# MAIN_STM32L476RGT6.net
KiCad netlist of a schematic drawn in Altium Designer
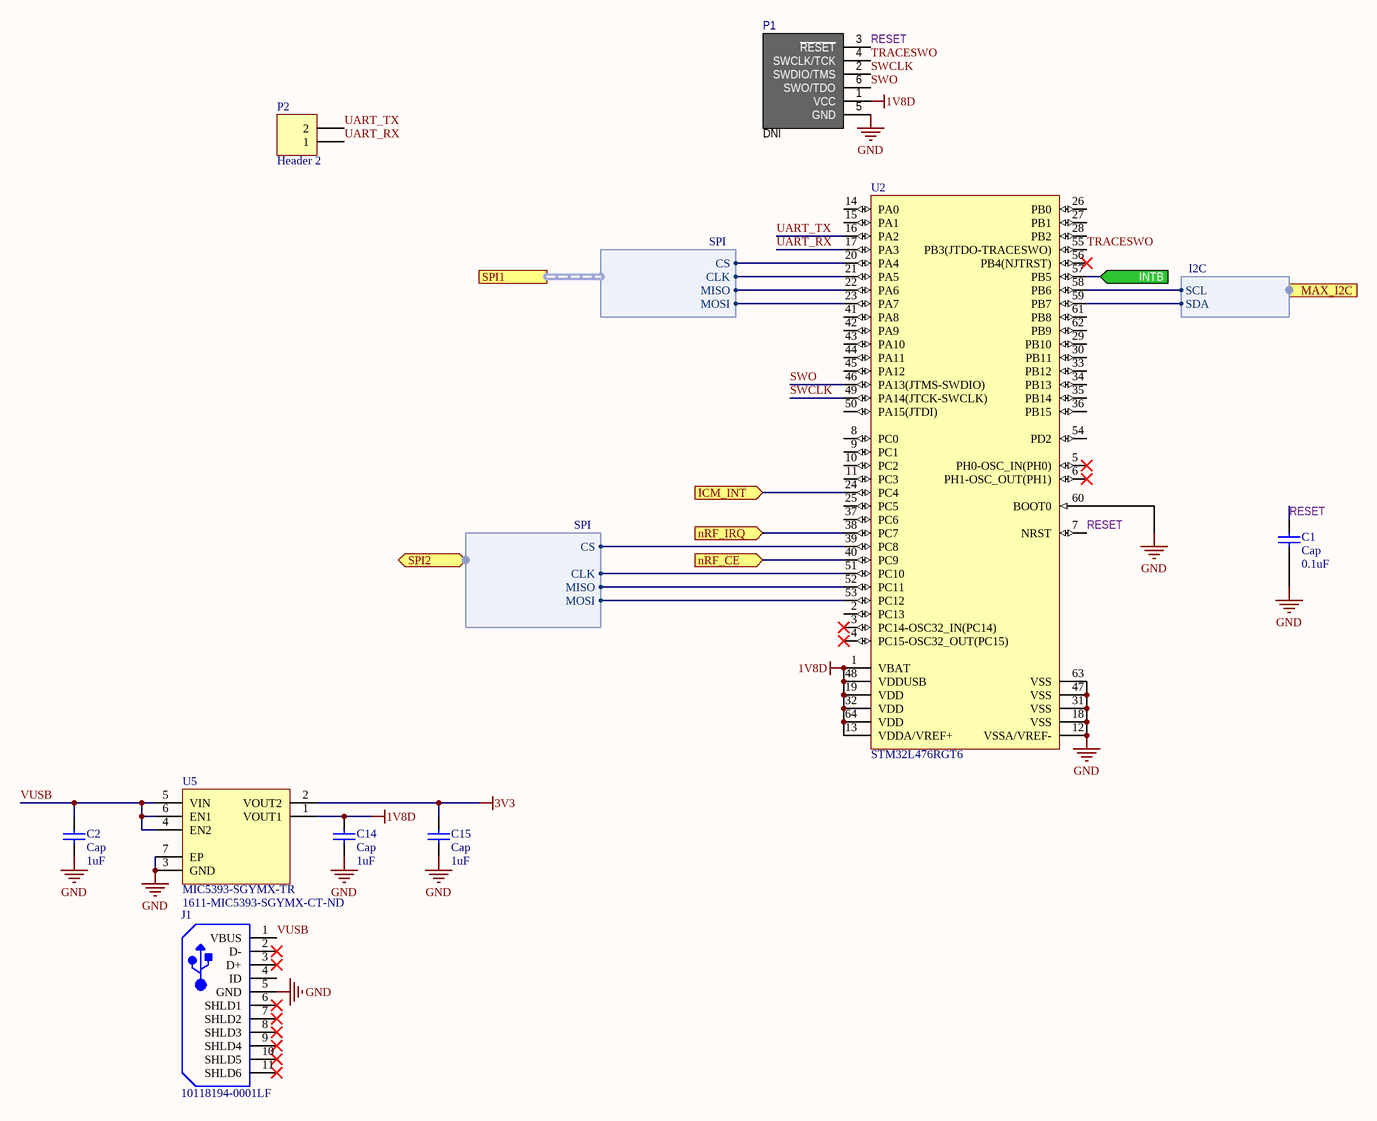
[diagram p0: MAIN_STM32L476RGT6.SchDoc]

(export (version "E")
  (design (tool "Eeschema 10.0.6"))
  (components
    (comp (ref "C1")
      (value "Cap")
      (footprint "CAPC1005N")
      (description "Capacitor")
      (fields (field (name "ALTIUM_VALUE") "0.1uF") (field (name "PUBLISHER") "Altium Limited"))
      (libsource (lib "Miscellaneous Devices") (part "Cap"))
    )
    (comp (ref "C2")
      (value "Cap")
      (footprint "CAPC1005N")
      (description "Capacitor")
      (fields (field (name "ALTIUM_VALUE") "1uF") (field (name "PUBLISHER") "Altium Limited"))
      (libsource (lib "Miscellaneous Devices") (part "Cap"))
    )
    (comp (ref "C14")
      (value "Cap")
      (footprint "CAPC1005N")
      (description "Capacitor")
      (fields (field (name "ALTIUM_VALUE") "1uF") (field (name "PUBLISHER") "Altium Limited"))
      (libsource (lib "Miscellaneous Devices") (part "Cap"))
    )
    (comp (ref "C15")
      (value "Cap")
      (footprint "CAPC1005N")
      (description "Capacitor")
      (fields (field (name "ALTIUM_VALUE") "1uF") (field (name "PUBLISHER") "Altium Limited"))
      (libsource (lib "Miscellaneous Devices") (part "Cap"))
    )
    (comp (ref "J1")
      (value "10118194-0001LF")
      (footprint "FCI-10118194-0001LF-5_V")
      (description "Micro USB B Type Receptacle, 1.8 A, -55 to 85 degC, 5-Pin SMD, RoHS, Tape and Reel")
      (fields (field (name "MANUFACTURER") "Amphenol FCI"))
      (libsource (lib "Altium Content Vault") (part "USB-5-6SHLD"))
    )
    (comp (ref "P1") (value "DNI") (footprint "TC2030") (libsource (lib "TagConnect") (part "TC2030-CTX")))
    (comp (ref "P2")
      (value "Header 2")
      (footprint "HDR1X2-PINS")
      (description "Header, 2-Pin")
      (fields (field (name "PUBLISHER") "Altium Limited"))
      (libsource (lib "Miscellaneous Connectors") (part "Header 2"))
    )
    (comp (ref "U2")
      (value "STM32L476RGT6")
      (footprint "STM-LQFP64_N")
      (fields (field (name "MANUFACTURER") "STMicroelectronics"))
      (libsource (lib "Altium Content Vault") (part "MC-ARM-STM32L4X6-LQFP64"))
    )
    (comp (ref "U5")
      (value "MIC5393-SGYMX-TR")
      (footprint "MIC5392")
      (description "IC REG LINEAR 1.8V/3.3V 6XTDFN")
      (fields (field (name "SUPPLIER PART NUMBER 1") "1611-MIC5393-SGYMX-CT-ND"))
      (libsource (lib "Schlib1") (part "MIC5393-SGYMX-TR"))
    )
  )
  (nets
    (net (code "3") (name "/ICM_INT") (class "Default")
      (node (ref "U2") (pin "24") (pinfunction "PC4_24") (pintype "bidirectional"))
    )
    (net (code "4") (name "/INTB") (class "Default")
      (node (ref "U2") (pin "57") (pinfunction "PB5_57") (pintype "bidirectional"))
    )
    (net (code "5") (name "/RESET") (class "Default")
      (node (ref "C1") (pin "2") (pinfunction "2_2") (pintype "passive"))
      (node (ref "P1") (pin "3") (pinfunction "~{RESET}_3") (pintype "passive"))
      (node (ref "U2") (pin "7") (pinfunction "NRST_7") (pintype "bidirectional"))
    )
    (net (code "6") (name "/SCL") (class "Default")
      (node (ref "U2") (pin "58") (pinfunction "PB6_58") (pintype "bidirectional"))
    )
    (net (code "7") (name "/SDA") (class "Default")
      (node (ref "U2") (pin "59") (pinfunction "PB7_59") (pintype "bidirectional"))
    )
    (net (code "8") (name "/SWCLK") (class "Default")
      (node (ref "P1") (pin "2") (pinfunction "SWDIO/TMS_2") (pintype "passive"))
      (node (ref "U2") (pin "49") (pinfunction "PA14(JTCK-SWCLK)_49") (pintype "bidirectional"))
    )
    (net (code "9") (name "/SWO") (class "Default")
      (node (ref "P1") (pin "6") (pinfunction "SWO/TDO_6") (pintype "passive"))
      (node (ref "U2") (pin "46") (pinfunction "PA13(JTMS-SWDIO)_46") (pintype "bidirectional"))
    )
    (net (code "10") (name "/TRACESWO") (class "Default")
      (node (ref "P1") (pin "4") (pinfunction "SWCLK/TCK_4") (pintype "passive"))
      (node (ref "U2") (pin "55") (pinfunction "PB3(JTDO-TRACESWO)_55") (pintype "bidirectional"))
    )
    (net (code "11") (name "/UART_RX") (class "Default")
      (node (ref "P2") (pin "1") (pinfunction "1_1") (pintype "passive"))
      (node (ref "U2") (pin "17") (pinfunction "PA3_17") (pintype "bidirectional"))
    )
    (net (code "12") (name "/UART_TX") (class "Default")
      (node (ref "P2") (pin "2") (pinfunction "2_2") (pintype "passive"))
      (node (ref "U2") (pin "16") (pinfunction "PA2_16") (pintype "bidirectional"))
    )
    (net (code "13") (name "/VUSB") (class "Default")
      (node (ref "C2") (pin "2") (pinfunction "2_2") (pintype "passive"))
      (node (ref "J1") (pin "1") (pinfunction "VBUS_1") (pintype "passive"))
      (node (ref "U5") (pin "4") (pinfunction "EN2_4") (pintype "passive"))
      (node (ref "U5") (pin "5") (pinfunction "VIN_5") (pintype "passive"))
      (node (ref "U5") (pin "6") (pinfunction "EN1_6") (pintype "passive"))
    )
    (net (code "14") (name "/nRF_CE") (class "Default")
      (node (ref "U2") (pin "40") (pinfunction "PC9_40") (pintype "bidirectional"))
    )
    (net (code "15") (name "/nRF_IRQ") (class "Default")
      (node (ref "U2") (pin "38") (pinfunction "PC7_38") (pintype "bidirectional"))
    )
    (net (code "18") (name "1V8D") (class "Default")
      (node (ref "C14") (pin "2") (pinfunction "2_2") (pintype "passive"))
      (node (ref "P1") (pin "1") (pinfunction "VCC_1") (pintype "passive"))
      (node (ref "U2") (pin "1") (pinfunction "VBAT_1") (pintype "power_in"))
      (node (ref "U2") (pin "13") (pinfunction "VDDA/VREF+_13") (pintype "power_in"))
      (node (ref "U2") (pin "19") (pinfunction "VDD_19") (pintype "power_in"))
      (node (ref "U2") (pin "32") (pinfunction "VDD_32") (pintype "power_in"))
      (node (ref "U2") (pin "48") (pinfunction "VDDUSB_48") (pintype "power_in"))
      (node (ref "U2") (pin "64") (pinfunction "VDD_64") (pintype "power_in"))
      (node (ref "U5") (pin "1") (pinfunction "VOUT1_1") (pintype "passive"))
    )
    (net (code "19") (name "3V3") (class "Default")
      (node (ref "C15") (pin "2") (pinfunction "2_2") (pintype "passive"))
      (node (ref "U5") (pin "2") (pinfunction "VOUT2_2") (pintype "passive"))
    )
    (net (code "20") (name "GND") (class "Default")
      (node (ref "C1") (pin "1") (pinfunction "1_1") (pintype "passive"))
      (node (ref "C14") (pin "1") (pinfunction "1_1") (pintype "passive"))
      (node (ref "C15") (pin "1") (pinfunction "1_1") (pintype "passive"))
      (node (ref "C2") (pin "1") (pinfunction "1_1") (pintype "passive"))
      (node (ref "J1") (pin "5") (pinfunction "GND_5") (pintype "passive"))
      (node (ref "P1") (pin "5") (pinfunction "GND_5") (pintype "passive"))
      (node (ref "U2") (pin "12") (pinfunction "VSSA/VREF-_12") (pintype "power_in"))
      (node (ref "U2") (pin "18") (pinfunction "VSS_18") (pintype "power_in"))
      (node (ref "U2") (pin "31") (pinfunction "VSS_31") (pintype "power_in"))
      (node (ref "U2") (pin "47") (pinfunction "VSS_47") (pintype "power_in"))
      (node (ref "U2") (pin "60") (pinfunction "BOOT0_60") (pintype "input"))
      (node (ref "U2") (pin "63") (pinfunction "VSS_63") (pintype "power_in"))
      (node (ref "U5") (pin "3") (pinfunction "GND_3") (pintype "passive"))
      (node (ref "U5") (pin "7") (pinfunction "EP_7") (pintype "passive"))
    )
    (net (code "21") (name "unconnected-(J1-D+-Pad3)") (class "Default")
      (node (ref "J1") (pin "3") (pinfunction "D+_3") (pintype "passive+no_connect"))
    )
    (net (code "22") (name "unconnected-(J1-D--Pad2)") (class "Default")
      (node (ref "J1") (pin "2") (pinfunction "D-_2") (pintype "passive+no_connect"))
    )
    (net (code "23") (name "unconnected-(J1-ID-Pad4)") (class "Default")
      (node (ref "J1") (pin "4") (pinfunction "ID_4") (pintype "passive"))
    )
    (net (code "24") (name "unconnected-(J1-SHLD1-Pad6)") (class "Default")
      (node (ref "J1") (pin "6") (pinfunction "SHLD1_6") (pintype "passive+no_connect"))
    )
    (net (code "25") (name "unconnected-(J1-SHLD2-Pad7)") (class "Default")
      (node (ref "J1") (pin "7") (pinfunction "SHLD2_7") (pintype "passive+no_connect"))
    )
    (net (code "26") (name "unconnected-(J1-SHLD3-Pad8)") (class "Default")
      (node (ref "J1") (pin "8") (pinfunction "SHLD3_8") (pintype "passive+no_connect"))
    )
    (net (code "27") (name "unconnected-(J1-SHLD4-Pad9)") (class "Default")
      (node (ref "J1") (pin "9") (pinfunction "SHLD4_9") (pintype "passive+no_connect"))
    )
    (net (code "28") (name "unconnected-(J1-SHLD5-Pad10)") (class "Default")
      (node (ref "J1") (pin "10") (pinfunction "SHLD5_10") (pintype "passive+no_connect"))
    )
    (net (code "29") (name "unconnected-(J1-SHLD6-Pad11)") (class "Default")
      (node (ref "J1") (pin "11") (pinfunction "SHLD6_11") (pintype "passive+no_connect"))
    )
    (net (code "30") (name "unconnected-(U2-PA0-Pad14)") (class "Default")
      (node (ref "U2") (pin "14") (pinfunction "PA0_14") (pintype "bidirectional"))
    )
    (net (code "31") (name "unconnected-(U2-PA1-Pad15)") (class "Default")
      (node (ref "U2") (pin "15") (pinfunction "PA1_15") (pintype "bidirectional"))
    )
    (net (code "32") (name "unconnected-(U2-PA4-Pad20)") (class "Default")
      (node (ref "U2") (pin "20") (pinfunction "PA4_20") (pintype "bidirectional"))
    )
    (net (code "33") (name "unconnected-(U2-PA5-Pad21)") (class "Default")
      (node (ref "U2") (pin "21") (pinfunction "PA5_21") (pintype "bidirectional"))
    )
    (net (code "34") (name "unconnected-(U2-PA6-Pad22)") (class "Default")
      (node (ref "U2") (pin "22") (pinfunction "PA6_22") (pintype "bidirectional"))
    )
    (net (code "35") (name "unconnected-(U2-PA7-Pad23)") (class "Default")
      (node (ref "U2") (pin "23") (pinfunction "PA7_23") (pintype "bidirectional"))
    )
    (net (code "36") (name "unconnected-(U2-PA8-Pad41)") (class "Default")
      (node (ref "U2") (pin "41") (pinfunction "PA8_41") (pintype "bidirectional"))
    )
    (net (code "37") (name "unconnected-(U2-PA9-Pad42)") (class "Default")
      (node (ref "U2") (pin "42") (pinfunction "PA9_42") (pintype "bidirectional"))
    )
    (net (code "38") (name "unconnected-(U2-PA10-Pad43)") (class "Default")
      (node (ref "U2") (pin "43") (pinfunction "PA10_43") (pintype "bidirectional"))
    )
    (net (code "39") (name "unconnected-(U2-PA11-Pad44)") (class "Default")
      (node (ref "U2") (pin "44") (pinfunction "PA11_44") (pintype "bidirectional"))
    )
    (net (code "40") (name "unconnected-(U2-PA12-Pad45)") (class "Default")
      (node (ref "U2") (pin "45") (pinfunction "PA12_45") (pintype "bidirectional"))
    )
    (net (code "41") (name "unconnected-(U2-PA15(JTDI)-Pad50)") (class "Default")
      (node (ref "U2") (pin "50") (pinfunction "PA15(JTDI)_50") (pintype "bidirectional"))
    )
    (net (code "42") (name "unconnected-(U2-PB0-Pad26)") (class "Default")
      (node (ref "U2") (pin "26") (pinfunction "PB0_26") (pintype "bidirectional"))
    )
    (net (code "43") (name "unconnected-(U2-PB1-Pad27)") (class "Default")
      (node (ref "U2") (pin "27") (pinfunction "PB1_27") (pintype "bidirectional"))
    )
    (net (code "44") (name "unconnected-(U2-PB2-Pad28)") (class "Default")
      (node (ref "U2") (pin "28") (pinfunction "PB2_28") (pintype "bidirectional"))
    )
    (net (code "45") (name "unconnected-(U2-PB4(NJTRST)-Pad56)") (class "Default")
      (node (ref "U2") (pin "56") (pinfunction "PB4(NJTRST)_56") (pintype "bidirectional+no_connect"))
    )
    (net (code "46") (name "unconnected-(U2-PB8-Pad61)") (class "Default")
      (node (ref "U2") (pin "61") (pinfunction "PB8_61") (pintype "bidirectional"))
    )
    (net (code "47") (name "unconnected-(U2-PB9-Pad62)") (class "Default")
      (node (ref "U2") (pin "62") (pinfunction "PB9_62") (pintype "bidirectional"))
    )
    (net (code "48") (name "unconnected-(U2-PB10-Pad29)") (class "Default")
      (node (ref "U2") (pin "29") (pinfunction "PB10_29") (pintype "bidirectional"))
    )
    (net (code "49") (name "unconnected-(U2-PB11-Pad30)") (class "Default")
      (node (ref "U2") (pin "30") (pinfunction "PB11_30") (pintype "bidirectional"))
    )
    (net (code "50") (name "unconnected-(U2-PB12-Pad33)") (class "Default")
      (node (ref "U2") (pin "33") (pinfunction "PB12_33") (pintype "bidirectional"))
    )
    (net (code "51") (name "unconnected-(U2-PB13-Pad34)") (class "Default")
      (node (ref "U2") (pin "34") (pinfunction "PB13_34") (pintype "bidirectional"))
    )
    (net (code "52") (name "unconnected-(U2-PB14-Pad35)") (class "Default")
      (node (ref "U2") (pin "35") (pinfunction "PB14_35") (pintype "bidirectional"))
    )
    (net (code "53") (name "unconnected-(U2-PB15-Pad36)") (class "Default")
      (node (ref "U2") (pin "36") (pinfunction "PB15_36") (pintype "bidirectional"))
    )
    (net (code "54") (name "unconnected-(U2-PC0-Pad8)") (class "Default")
      (node (ref "U2") (pin "8") (pinfunction "PC0_8") (pintype "bidirectional"))
    )
    (net (code "55") (name "unconnected-(U2-PC1-Pad9)") (class "Default")
      (node (ref "U2") (pin "9") (pinfunction "PC1_9") (pintype "bidirectional"))
    )
    (net (code "56") (name "unconnected-(U2-PC2-Pad10)") (class "Default")
      (node (ref "U2") (pin "10") (pinfunction "PC2_10") (pintype "bidirectional"))
    )
    (net (code "57") (name "unconnected-(U2-PC3-Pad11)") (class "Default")
      (node (ref "U2") (pin "11") (pinfunction "PC3_11") (pintype "bidirectional"))
    )
    (net (code "58") (name "unconnected-(U2-PC5-Pad25)") (class "Default")
      (node (ref "U2") (pin "25") (pinfunction "PC5_25") (pintype "bidirectional"))
    )
    (net (code "59") (name "unconnected-(U2-PC6-Pad37)") (class "Default")
      (node (ref "U2") (pin "37") (pinfunction "PC6_37") (pintype "bidirectional"))
    )
    (net (code "60") (name "unconnected-(U2-PC8-Pad39)") (class "Default")
      (node (ref "U2") (pin "39") (pinfunction "PC8_39") (pintype "bidirectional"))
    )
    (net (code "61") (name "unconnected-(U2-PC10-Pad51)") (class "Default")
      (node (ref "U2") (pin "51") (pinfunction "PC10_51") (pintype "bidirectional"))
    )
    (net (code "62") (name "unconnected-(U2-PC11-Pad52)") (class "Default")
      (node (ref "U2") (pin "52") (pinfunction "PC11_52") (pintype "bidirectional"))
    )
    (net (code "63") (name "unconnected-(U2-PC12-Pad53)") (class "Default")
      (node (ref "U2") (pin "53") (pinfunction "PC12_53") (pintype "bidirectional"))
    )
    (net (code "64") (name "unconnected-(U2-PC13-Pad2)") (class "Default")
      (node (ref "U2") (pin "2") (pinfunction "PC13_2") (pintype "bidirectional"))
    )
    (net (code "65") (name "unconnected-(U2-PC14-OSC32_IN(PC14)-Pad3)") (class "Default")
      (node (ref "U2") (pin "3") (pinfunction "PC14-OSC32_IN(PC14)_3") (pintype "bidirectional+no_connect"))
    )
    (net (code "66") (name "unconnected-(U2-PC15-OSC32_OUT(PC15)-Pad4)") (class "Default")
      (node (ref "U2") (pin "4") (pinfunction "PC15-OSC32_OUT(PC15)_4") (pintype "bidirectional+no_connect"))
    )
    (net (code "67") (name "unconnected-(U2-PD2-Pad54)") (class "Default")
      (node (ref "U2") (pin "54") (pinfunction "PD2_54") (pintype "bidirectional"))
    )
    (net (code "68") (name "unconnected-(U2-PH0-OSC_IN(PH0)-Pad5)") (class "Default")
      (node (ref "U2") (pin "5") (pinfunction "PH0-OSC_IN(PH0)_5") (pintype "bidirectional+no_connect"))
    )
    (net (code "69") (name "unconnected-(U2-PH1-OSC_OUT(PH1)-Pad6)") (class "Default")
      (node (ref "U2") (pin "6") (pinfunction "PH1-OSC_OUT(PH1)_6") (pintype "bidirectional+no_connect"))
    )
  )
)
